# FrontPanel.net
KiCad netlist of a schematic drawn in Altium Designer
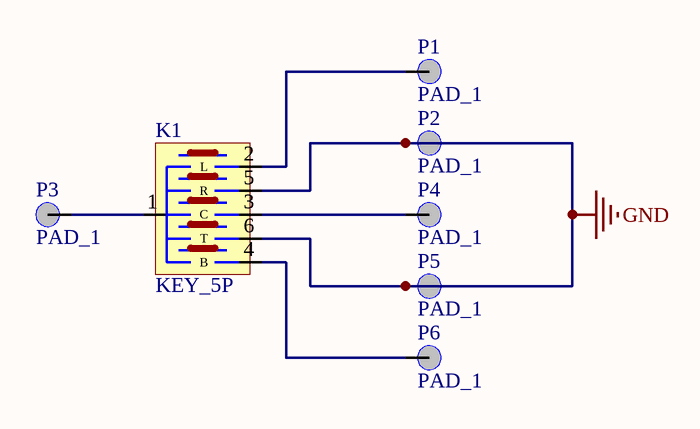
[diagram p0: FrontPanel.SchDoc]

(export (version "E")
  (design (tool "Eeschema 10.0.6"))
  (components
    (comp (ref "K1")
      (value "KEY_5P")
      (footprint "KEY_5")
      (description "五向开关")
      (libsource (lib "Levent_lib") (part "KEY_5P"))
    )
    (comp (ref "P1")
      (value "PAD_1")
      (footprint "Pad_Slot_1")
      (description "1脚焊盘")
      (libsource (lib "Levent_lib") (part "PAD_1"))
    )
    (comp (ref "P2")
      (value "PAD_1")
      (footprint "Pad_Pin_1")
      (description "1脚焊盘")
      (libsource (lib "Levent_lib") (part "PAD_1"))
    )
    (comp (ref "P3")
      (value "PAD_1")
      (footprint "Pad_Slot_1")
      (description "1脚焊盘")
      (libsource (lib "Levent_lib") (part "PAD_1"))
    )
    (comp (ref "P4")
      (value "PAD_1")
      (footprint "Pad_Slot_1")
      (description "1脚焊盘")
      (libsource (lib "Levent_lib") (part "PAD_1"))
    )
    (comp (ref "P5")
      (value "PAD_1")
      (footprint "Pad_Pin_1")
      (description "1脚焊盘")
      (libsource (lib "Levent_lib") (part "PAD_1"))
    )
    (comp (ref "P6")
      (value "PAD_1")
      (footprint "Pad_Slot_1")
      (description "1脚焊盘")
      (libsource (lib "Levent_lib") (part "PAD_1"))
    )
  )
  (nets
    (net (code "1") (name "GND") (class "Default")
      (node (ref "K1") (pin "5") (pinfunction "R_5") (pintype "passive"))
      (node (ref "K1") (pin "6") (pinfunction "T_6") (pintype "passive"))
      (node (ref "P2") (pin "1") (pinfunction "1_1") (pintype "passive"))
      (node (ref "P5") (pin "1") (pinfunction "1_1") (pintype "passive"))
    )
    (net (code "2") (name "Net-(K1-B)") (class "Default")
      (node (ref "K1") (pin "4") (pinfunction "B_4") (pintype "passive"))
      (node (ref "P6") (pin "1") (pinfunction "1_1") (pintype "passive"))
    )
    (net (code "3") (name "Net-(K1-C)") (class "Default")
      (node (ref "K1") (pin "3") (pinfunction "C_3") (pintype "passive"))
      (node (ref "P4") (pin "1") (pinfunction "1_1") (pintype "passive"))
    )
    (net (code "4") (name "Net-(K1-G)") (class "Default")
      (node (ref "K1") (pin "1") (pinfunction "G_1") (pintype "passive"))
      (node (ref "P3") (pin "1") (pinfunction "1_1") (pintype "passive"))
    )
    (net (code "5") (name "Net-(K1-L)") (class "Default")
      (node (ref "K1") (pin "2") (pinfunction "L_2") (pintype "passive"))
      (node (ref "P1") (pin "1") (pinfunction "1_1") (pintype "passive"))
    )
  )
)
